# Heated_Bed.net
KiCad netlist of a schematic drawn in EAGLE
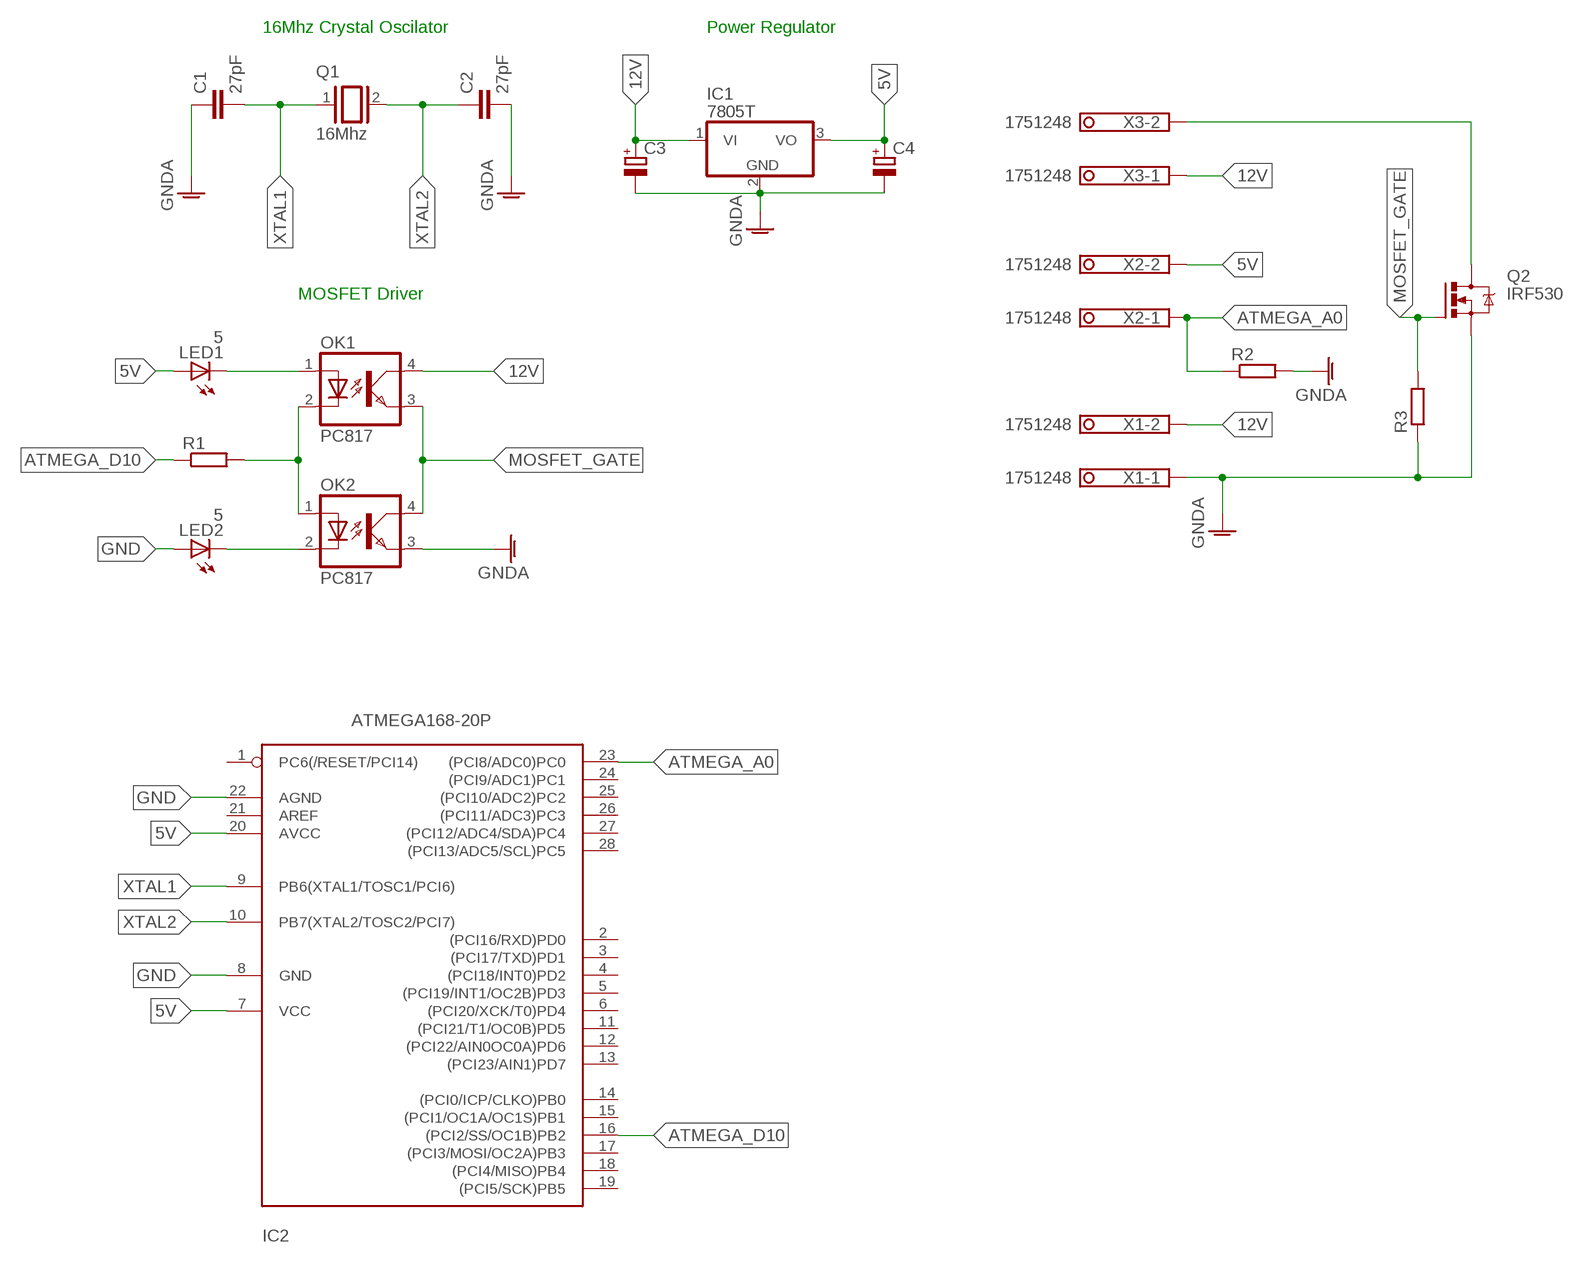
[diagram p0: schematic, sheet 1]

(export (version "E")
  (design (tool "Eeschema 10.0.6"))
  (components
    (comp (ref "C1")
      (value "27pF")
      (footprint "eagle-import:C025-025X050")
      (libsource (lib "eagle-import") (part "C-EU025-025X050"))
    )
    (comp (ref "C2")
      (value "27pF")
      (footprint "eagle-import:C025-025X050")
      (libsource (lib "eagle-import") (part "C-EU025-025X050"))
    )
    (comp (ref "C3")
      (value "CPOL-EUE5-10.5")
      (footprint "eagle-import:E5-10,5")
      (libsource (lib "eagle-import") (part "CPOL-EUE5-10.5"))
    )
    (comp (ref "C4")
      (value "CPOL-EUE5-10.5")
      (footprint "eagle-import:E5-10,5")
      (libsource (lib "eagle-import") (part "CPOL-EUE5-10.5"))
    )
    (comp (ref "IC1")
      (value "7805T")
      (footprint "eagle-import:TO220H")
      (libsource (lib "eagle-import") (part "78T05"))
    )
    (comp (ref "IC2")
      (value "ATMEGA168-20P")
      (footprint "eagle-import:DIL28-3")
      (libsource (lib "eagle-import") (part "ATMEGA168P-20"))
    )
    (comp (ref "LED1")
      (value "5")
      (footprint "eagle-import:LED5MM")
      (libsource (lib "eagle-import") (part "LED5MM"))
    )
    (comp (ref "LED2")
      (value "5")
      (footprint "eagle-import:LED5MM")
      (libsource (lib "eagle-import") (part "LED5MM"))
    )
    (comp (ref "OK1")
      (value "PC817")
      (footprint "eagle-import:DIL04")
      (fields (field (name "MPN") "PC817X4J000F"))
      (libsource (lib "eagle-import") (part "PC817"))
    )
    (comp (ref "OK2")
      (value "PC817")
      (footprint "eagle-import:DIL04")
      (fields (field (name "MPN") "PC817X4J000F"))
      (libsource (lib "eagle-import") (part "PC817"))
    )
    (comp (ref "Q1")
      (value "16Mhz")
      (footprint "eagle-import:QS")
      (libsource (lib "eagle-import") (part "XTAL/S"))
    )
    (comp (ref "Q2")
      (value "IRF530")
      (footprint "eagle-import:TO220BV")
      (libsource (lib "eagle-import") (part "IRF530"))
    )
    (comp (ref "R1")
      (value "R-EU_0207/7")
      (footprint "eagle-import:0207_7")
      (libsource (lib "eagle-import") (part "R-EU_0207/7"))
    )
    (comp (ref "R2")
      (value "R-EU_0207/7")
      (footprint "eagle-import:0207_7")
      (libsource (lib "eagle-import") (part "R-EU_0207/7"))
    )
    (comp (ref "R3")
      (value "R-EU_0207/7")
      (footprint "eagle-import:0207_7")
      (libsource (lib "eagle-import") (part "R-EU_0207/7"))
    )
    (comp (ref "X1")
      (value "1751248")
      (footprint "eagle-import:1751248")
      (libsource (lib "eagle-import") (part "1751248"))
    )
    (comp (ref "X2")
      (value "1751248")
      (footprint "eagle-import:1751248")
      (libsource (lib "eagle-import") (part "1751248"))
    )
    (comp (ref "X3")
      (value "1751248")
      (footprint "eagle-import:1751248")
      (libsource (lib "eagle-import") (part "1751248"))
    )
  )
  (nets
    (net (code "1") (name "5V") (class "Default")
      (node (ref "C4") (pin "+") (pinfunction "+_+") (pintype "passive"))
      (node (ref "IC1") (pin "3") (pinfunction "VO_3") (pintype "passive"))
      (node (ref "IC2") (pin "20") (pinfunction "AVCC_20") (pintype "bidirectional"))
      (node (ref "IC2") (pin "7") (pinfunction "VCC_7") (pintype "bidirectional"))
      (node (ref "LED1") (pin "A") (pinfunction "A_A") (pintype "passive"))
      (node (ref "X2") (pin "2") (pinfunction "K_2") (pintype "passive"))
    )
    (net (code "2") (name "12V") (class "Default")
      (node (ref "C3") (pin "+") (pinfunction "+_+") (pintype "passive"))
      (node (ref "IC1") (pin "1") (pinfunction "VI_1") (pintype "input"))
      (node (ref "OK1") (pin "4") (pinfunction "COL_4") (pintype "passive"))
      (node (ref "X1") (pin "2") (pinfunction "K_2") (pintype "passive"))
      (node (ref "X3") (pin "1") (pinfunction "K_1") (pintype "passive"))
    )
    (net (code "3") (name "ATMEGA_A0") (class "Default")
      (node (ref "IC2") (pin "23") (pinfunction "(PCI8/ADC0)PC0_23") (pintype "bidirectional"))
      (node (ref "R2") (pin "1") (pinfunction "1_1") (pintype "passive"))
      (node (ref "X2") (pin "1") (pinfunction "K_1") (pintype "passive"))
    )
    (net (code "4") (name "ATMEGA_D10") (class "Default")
      (node (ref "IC2") (pin "16") (pinfunction "(PCI2/SS/OC1B)PB2_16") (pintype "bidirectional"))
      (node (ref "R1") (pin "1") (pinfunction "1_1") (pintype "passive"))
    )
    (net (code "5") (name "GND") (class "Default")
      (node (ref "C1") (pin "1") (pinfunction "1_1") (pintype "passive"))
      (node (ref "C2") (pin "2") (pinfunction "2_2") (pintype "passive"))
      (node (ref "C3") (pin "-") (pinfunction "-_-") (pintype "passive"))
      (node (ref "C4") (pin "-") (pinfunction "-_-") (pintype "passive"))
      (node (ref "IC1") (pin "2") (pinfunction "GND_2") (pintype "passive"))
      (node (ref "IC2") (pin "22") (pinfunction "AGND_22") (pintype "bidirectional"))
      (node (ref "IC2") (pin "8") (pinfunction "GND_8") (pintype "bidirectional"))
      (node (ref "LED2") (pin "A") (pinfunction "A_A") (pintype "passive"))
      (node (ref "OK2") (pin "3") (pinfunction "EMIT_3") (pintype "passive"))
      (node (ref "Q2") (pin "S") (pinfunction "S_S") (pintype "passive"))
      (node (ref "R2") (pin "2") (pinfunction "2_2") (pintype "passive"))
      (node (ref "R3") (pin "1") (pinfunction "1_1") (pintype "passive"))
      (node (ref "X1") (pin "1") (pinfunction "K_1") (pintype "passive"))
    )
    (net (code "6") (name "MOSFET_GATE") (class "Default")
      (node (ref "OK1") (pin "3") (pinfunction "EMIT_3") (pintype "passive"))
      (node (ref "OK2") (pin "4") (pinfunction "COL_4") (pintype "passive"))
      (node (ref "Q2") (pin "G") (pinfunction "G_G") (pintype "passive"))
      (node (ref "R3") (pin "2") (pinfunction "2_2") (pintype "passive"))
    )
    (net (code "7") (name "Net-(LED1-C)") (class "Default")
      (node (ref "LED1") (pin "K") (pinfunction "C_K") (pintype "passive"))
      (node (ref "OK1") (pin "1") (pinfunction "A_1") (pintype "passive"))
    )
    (net (code "8") (name "Net-(LED2-C)") (class "Default")
      (node (ref "LED2") (pin "K") (pinfunction "C_K") (pintype "passive"))
      (node (ref "OK2") (pin "2") (pinfunction "C_2") (pintype "passive"))
    )
    (net (code "9") (name "Net-(OK1-C)") (class "Default")
      (node (ref "OK1") (pin "2") (pinfunction "C_2") (pintype "passive"))
      (node (ref "OK2") (pin "1") (pinfunction "A_1") (pintype "passive"))
      (node (ref "R1") (pin "2") (pinfunction "2_2") (pintype "passive"))
    )
    (net (code "10") (name "Net-(X3B-K)") (class "Default")
      (node (ref "Q2") (pin "D") (pinfunction "D_D") (pintype "passive"))
      (node (ref "X3") (pin "2") (pinfunction "K_2") (pintype "passive"))
    )
    (net (code "11") (name "XTAL1") (class "Default")
      (node (ref "C1") (pin "2") (pinfunction "2_2") (pintype "passive"))
      (node (ref "IC2") (pin "9") (pinfunction "PB6(XTAL1/TOSC1/PCI6)_9") (pintype "bidirectional"))
      (node (ref "Q1") (pin "1") (pinfunction "1_1") (pintype "passive"))
    )
    (net (code "12") (name "XTAL2") (class "Default")
      (node (ref "C2") (pin "1") (pinfunction "1_1") (pintype "passive"))
      (node (ref "IC2") (pin "10") (pinfunction "PB7(XTAL2/TOSC2/PCI7)_10") (pintype "bidirectional"))
      (node (ref "Q1") (pin "2") (pinfunction "2_2") (pintype "passive"))
    )
    (net (code "13") (name "unconnected-(IC2-(PCI0{slash}ICP{slash}CLKO)PB0-Pad14)") (class "Default")
      (node (ref "IC2") (pin "14") (pinfunction "(PCI0/ICP/CLKO)PB0_14") (pintype "bidirectional"))
    )
    (net (code "14") (name "unconnected-(IC2-(PCI1{slash}OC1A{slash}OC1S)PB1-Pad15)") (class "Default")
      (node (ref "IC2") (pin "15") (pinfunction "(PCI1/OC1A/OC1S)PB1_15") (pintype "bidirectional"))
    )
    (net (code "15") (name "unconnected-(IC2-(PCI3{slash}MOSI{slash}OC2A)PB3-Pad17)") (class "Default")
      (node (ref "IC2") (pin "17") (pinfunction "(PCI3/MOSI/OC2A)PB3_17") (pintype "bidirectional"))
    )
    (net (code "16") (name "unconnected-(IC2-(PCI4{slash}MISO)PB4-Pad18)") (class "Default")
      (node (ref "IC2") (pin "18") (pinfunction "(PCI4/MISO)PB4_18") (pintype "bidirectional"))
    )
    (net (code "17") (name "unconnected-(IC2-(PCI5{slash}SCK)PB5-Pad19)") (class "Default")
      (node (ref "IC2") (pin "19") (pinfunction "(PCI5/SCK)PB5_19") (pintype "bidirectional"))
    )
    (net (code "18") (name "unconnected-(IC2-(PCI9{slash}ADC1)PC1-Pad24)") (class "Default")
      (node (ref "IC2") (pin "24") (pinfunction "(PCI9/ADC1)PC1_24") (pintype "bidirectional"))
    )
    (net (code "19") (name "unconnected-(IC2-(PCI10{slash}ADC2)PC2-Pad25)") (class "Default")
      (node (ref "IC2") (pin "25") (pinfunction "(PCI10/ADC2)PC2_25") (pintype "bidirectional"))
    )
    (net (code "20") (name "unconnected-(IC2-(PCI11{slash}ADC3)PC3-Pad26)") (class "Default")
      (node (ref "IC2") (pin "26") (pinfunction "(PCI11/ADC3)PC3_26") (pintype "bidirectional"))
    )
    (net (code "21") (name "unconnected-(IC2-(PCI12{slash}ADC4{slash}SDA)PC4-Pad27)") (class "Default")
      (node (ref "IC2") (pin "27") (pinfunction "(PCI12/ADC4/SDA)PC4_27") (pintype "bidirectional"))
    )
    (net (code "22") (name "unconnected-(IC2-(PCI13{slash}ADC5{slash}SCL)PC5-Pad28)") (class "Default")
      (node (ref "IC2") (pin "28") (pinfunction "(PCI13/ADC5/SCL)PC5_28") (pintype "bidirectional"))
    )
    (net (code "23") (name "unconnected-(IC2-(PCI16{slash}RXD)PD0-Pad2)") (class "Default")
      (node (ref "IC2") (pin "2") (pinfunction "(PCI16/RXD)PD0_2") (pintype "bidirectional"))
    )
    (net (code "24") (name "unconnected-(IC2-(PCI17{slash}TXD)PD1-Pad3)") (class "Default")
      (node (ref "IC2") (pin "3") (pinfunction "(PCI17/TXD)PD1_3") (pintype "bidirectional"))
    )
    (net (code "25") (name "unconnected-(IC2-(PCI18{slash}INT0)PD2-Pad4)") (class "Default")
      (node (ref "IC2") (pin "4") (pinfunction "(PCI18/INT0)PD2_4") (pintype "bidirectional"))
    )
    (net (code "26") (name "unconnected-(IC2-(PCI19{slash}INT1{slash}OC2B)PD3-Pad5)") (class "Default")
      (node (ref "IC2") (pin "5") (pinfunction "(PCI19/INT1/OC2B)PD3_5") (pintype "bidirectional"))
    )
    (net (code "27") (name "unconnected-(IC2-(PCI20{slash}XCK{slash}T0)PD4-Pad6)") (class "Default")
      (node (ref "IC2") (pin "6") (pinfunction "(PCI20/XCK/T0)PD4_6") (pintype "bidirectional"))
    )
    (net (code "28") (name "unconnected-(IC2-(PCI21{slash}T1{slash}OC0B)PD5-Pad11)") (class "Default")
      (node (ref "IC2") (pin "11") (pinfunction "(PCI21/T1/OC0B)PD5_11") (pintype "bidirectional"))
    )
    (net (code "29") (name "unconnected-(IC2-(PCI22{slash}AIN0OC0A)PD6-Pad12)") (class "Default")
      (node (ref "IC2") (pin "12") (pinfunction "(PCI22/AIN0OC0A)PD6_12") (pintype "bidirectional"))
    )
    (net (code "30") (name "unconnected-(IC2-(PCI23{slash}AIN1)PD7-Pad13)") (class "Default")
      (node (ref "IC2") (pin "13") (pinfunction "(PCI23/AIN1)PD7_13") (pintype "bidirectional"))
    )
    (net (code "31") (name "unconnected-(IC2-AREF-Pad21)") (class "Default")
      (node (ref "IC2") (pin "21") (pinfunction "AREF_21") (pintype "bidirectional"))
    )
    (net (code "32") (name "unconnected-(IC2-PC6({slash}RESET{slash}PCI14)-Pad1)") (class "Default")
      (node (ref "IC2") (pin "1") (pinfunction "PC6(/RESET/PCI14)_1") (pintype "bidirectional"))
    )
  )
)
